# Kasli-SOC_top.net
KiCad netlist of a schematic drawn in Altium Designer
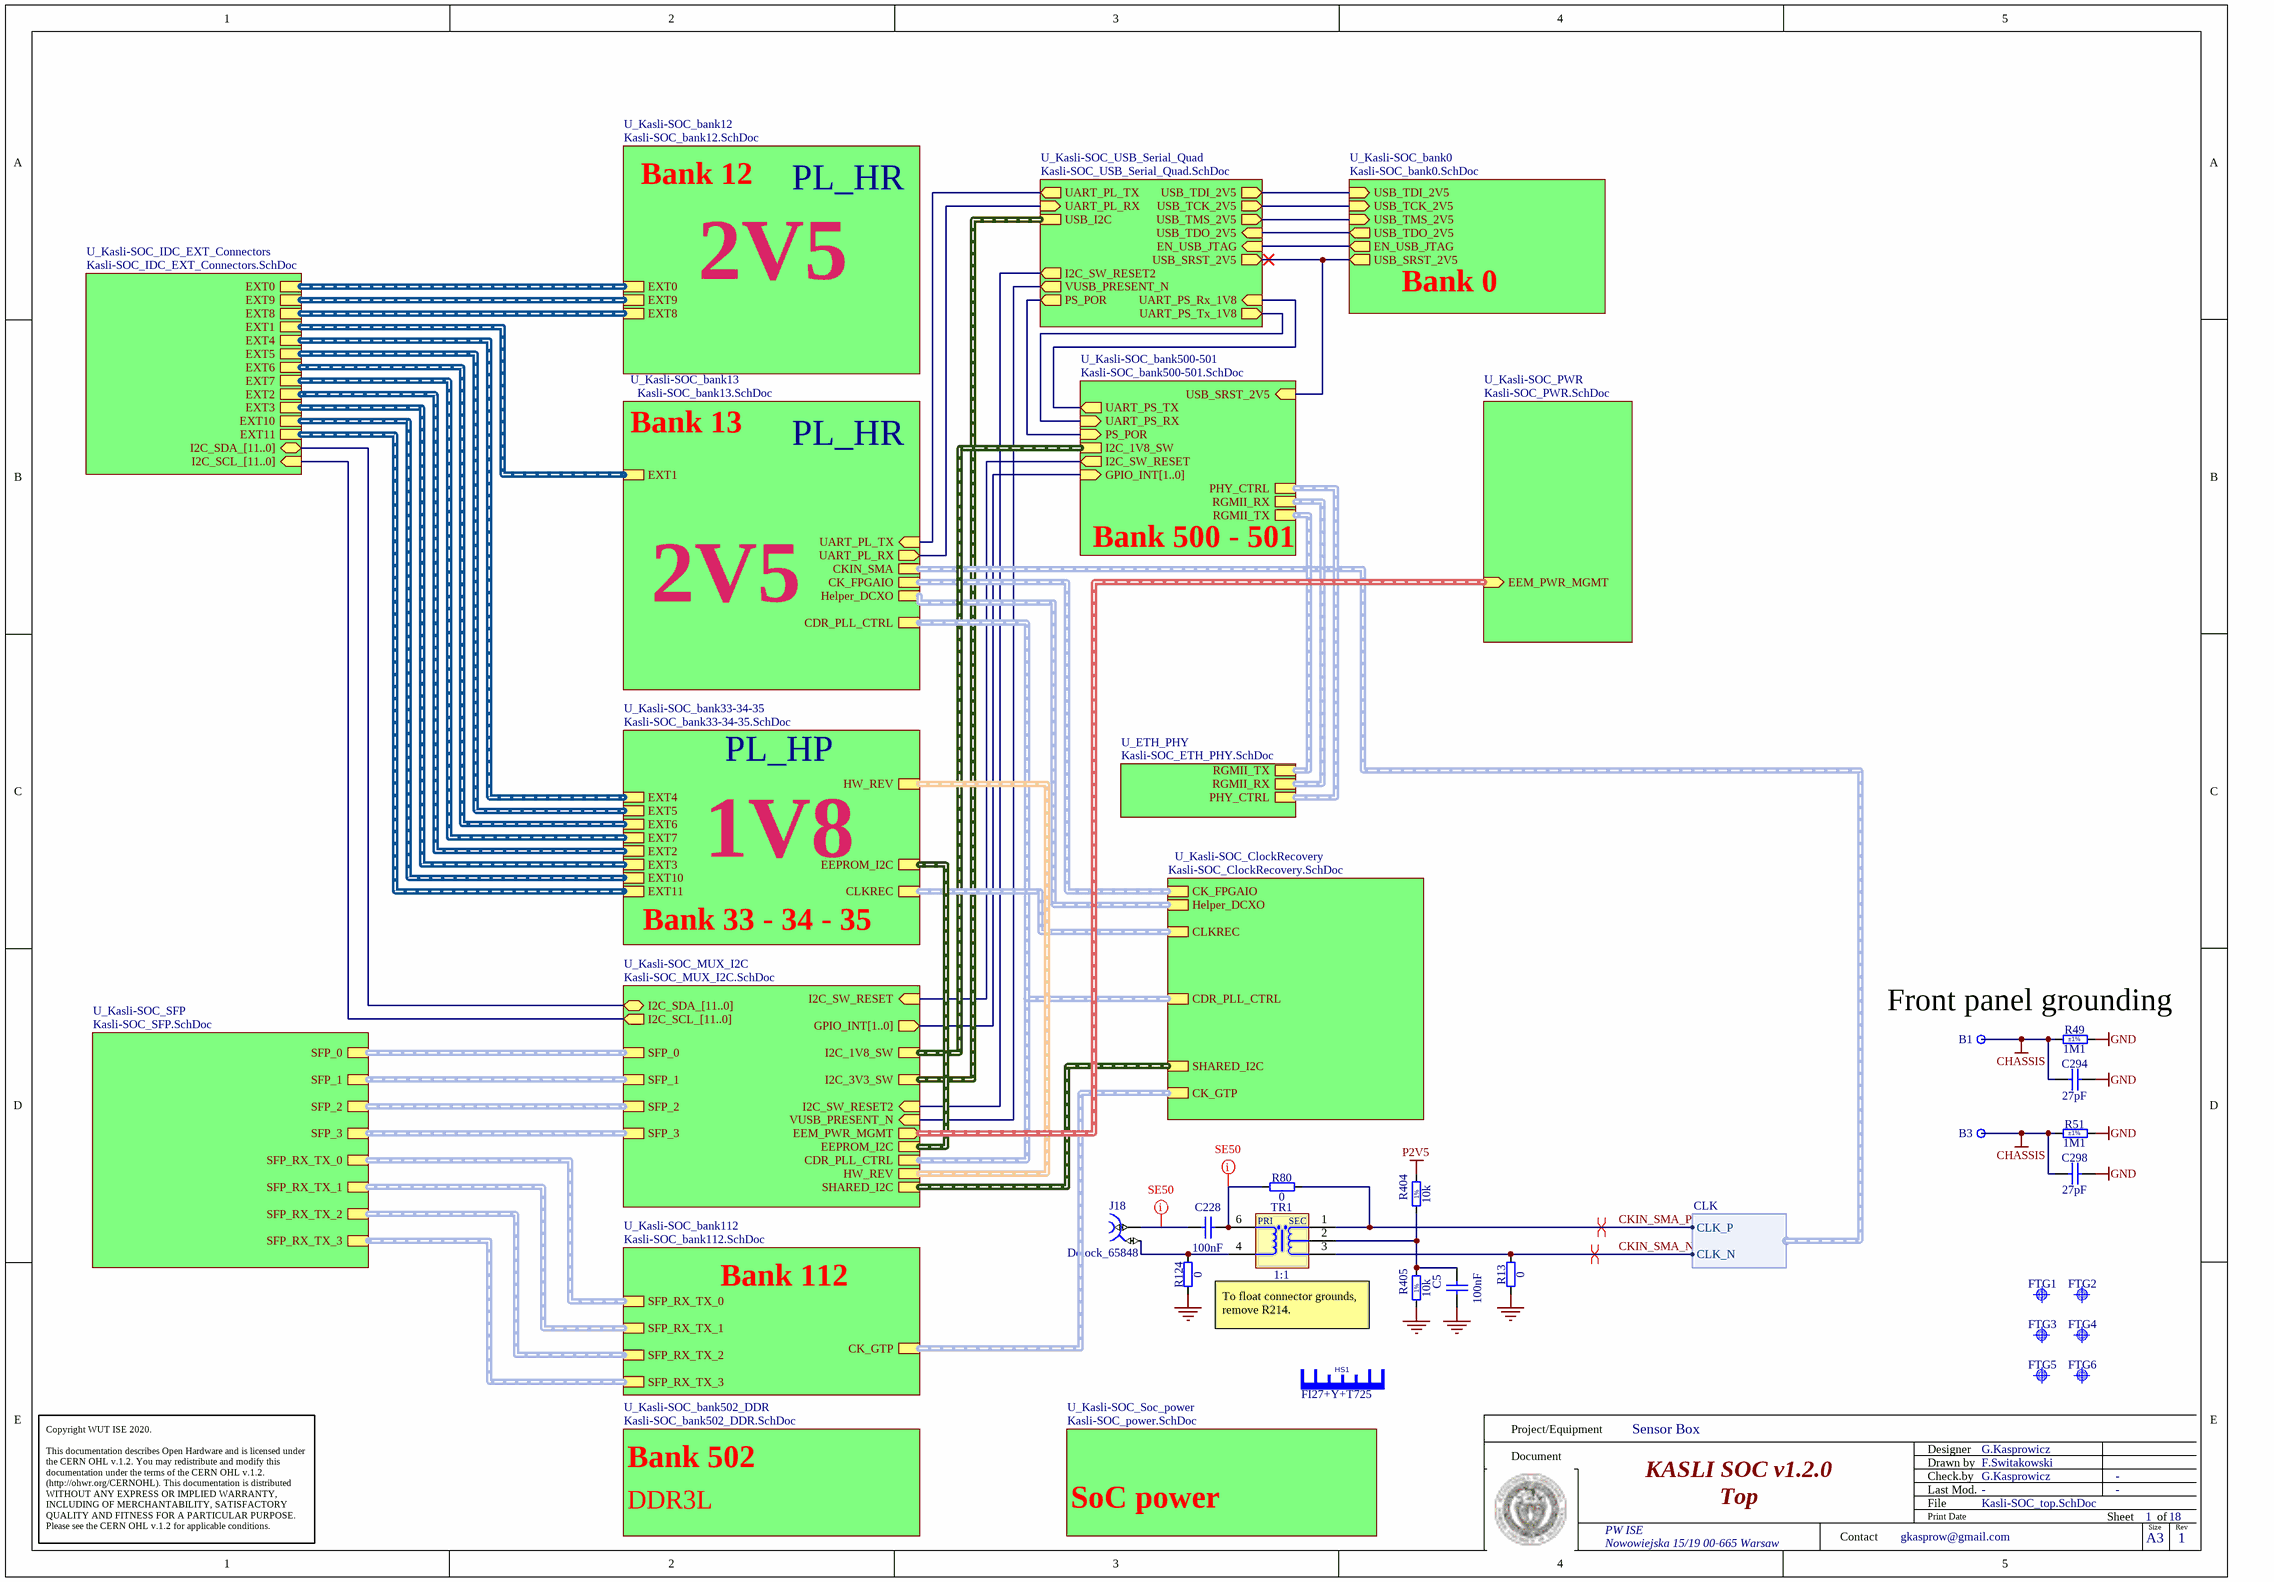
[diagram p0: Kasli-SOC_top.SchDoc]

(export (version "E")
  (design (tool "Eeschema 10.0.6"))
  (components
    (comp (ref "B1")
      (value "Plated Hole")
      (footprint "MTG270_500")
      (description "Single Terminal Socket")
      (fields (field (name "PART NUMBER") "PLATED_HOLE2.7_PAD5.0") (field (name "AUTHOR") "CERN DEM JMW"))
      (libsource (lib "Eletro-mechanical") (part "Single Terminal Socket"))
    )
    (comp (ref "B3")
      (value "Plated Hole")
      (footprint "MTG270_500")
      (description "Single Terminal Socket")
      (fields (field (name "PART NUMBER") "PLATED_HOLE2.7_PAD5.0") (field (name "AUTHOR") "CERN DEM JMW"))
      (libsource (lib "Eletro-mechanical") (part "Single Terminal Socket"))
    )
    (comp (ref "C5")
      (value "100nF")
      (footprint "CAPC0603X33N")
      (description "Non-polarised capacitor")
      (fields
        (field (name "PART NUMBER") "CC0201_100NF_6.3V_10%_X5R")
        (field (name "VOLTAGE") "6.3V")
        (field (name "AUTHOR") "CERN DEM JLC")
      )
      (libsource (lib "Capacitors") (part "Capacitor - non polarized"))
    )
    (comp (ref "C228")
      (value "100nF")
      (footprint "CAPC0603X33N")
      (description "Non-polarised capacitor")
      (fields
        (field (name "PART NUMBER") "CC0201_100NF_6.3V_10%_X5R")
        (field (name "VOLTAGE") "6.3V")
        (field (name "AUTHOR") "CERN DEM JLC")
      )
      (libsource (lib "Capacitors") (part "Capacitor - non polarized"))
    )
    (comp (ref "C294")
      (value "27pF")
      (footprint "CAPC2012X135N")
      (description "Non-polarised capacitor")
      (fields
        (field (name "PART NUMBER") "CC0805_27PF_50V_5%_NP0")
        (field (name "VOLTAGE") "50V")
        (field (name "AUTHOR") "CERN DEM JLC")
      )
      (libsource (lib "Capacitors") (part "Capacitor - non polarized"))
    )
    (comp (ref "C298")
      (value "27pF")
      (footprint "CAPC2012X135N")
      (description "Non-polarised capacitor")
      (fields
        (field (name "PART NUMBER") "CC0805_27PF_50V_5%_NP0")
        (field (name "VOLTAGE") "50V")
        (field (name "AUTHOR") "CERN DEM JLC")
      )
      (libsource (lib "Capacitors") (part "Capacitor - non polarized"))
    )
    (comp (ref "FTG1")
      (value "Use only in PCB")
      (footprint "FIDUCIAL_TOP_S100-200")
      (description "Fiducial Target")
      (fields (field (name "PART NUMBER") "FIDUCIAL_TARGET_S100-200") (field (name "AUTHOR") "CERN DEM JLC"))
      (libsource (lib "Eletro-mechanical") (part "Fiducial Target"))
    )
    (comp (ref "FTG2")
      (value "Use only in PCB")
      (footprint "FIDUCIAL_TOP_S100-200")
      (description "Fiducial Target")
      (fields (field (name "PART NUMBER") "FIDUCIAL_TARGET_S100-200") (field (name "AUTHOR") "CERN DEM JLC"))
      (libsource (lib "Eletro-mechanical") (part "Fiducial Target"))
    )
    (comp (ref "FTG3")
      (value "Use only in PCB")
      (footprint "FIDUCIAL_TOP_S100-200")
      (description "Fiducial Target")
      (fields (field (name "PART NUMBER") "FIDUCIAL_TARGET_S100-200") (field (name "AUTHOR") "CERN DEM JLC"))
      (libsource (lib "Eletro-mechanical") (part "Fiducial Target"))
    )
    (comp (ref "FTG4")
      (value "Use only in PCB")
      (footprint "FIDUCIAL_TOP_S100-200")
      (description "Fiducial Target")
      (fields (field (name "PART NUMBER") "FIDUCIAL_TARGET_S100-200") (field (name "AUTHOR") "CERN DEM JLC"))
      (libsource (lib "Eletro-mechanical") (part "Fiducial Target"))
    )
    (comp (ref "FTG5")
      (value "Use only in PCB")
      (footprint "FIDUCIAL_TOP_S100-200")
      (description "Fiducial Target")
      (fields (field (name "PART NUMBER") "FIDUCIAL_TARGET_S100-200") (field (name "AUTHOR") "CERN DEM JLC"))
      (libsource (lib "Eletro-mechanical") (part "Fiducial Target"))
    )
    (comp (ref "FTG6")
      (value "Use only in PCB")
      (footprint "FIDUCIAL_TOP_S100-200")
      (description "Fiducial Target")
      (fields (field (name "PART NUMBER") "FIDUCIAL_TARGET_S100-200") (field (name "AUTHOR") "CERN DEM JLC"))
      (libsource (lib "Eletro-mechanical") (part "Fiducial Target"))
    )
    (comp (ref "HS1")
      (value "RADIAN_FI27+Y+T725")
      (description "Heat Sink Without Pad")
      (fields
        (field (name "MANUFACTURER") "Radian Thermal Products, Inc.")
        (field (name "MANUFACTURER PART NUMBER") "FI27+Y+T725")
      )
      (libsource (lib "Schlib1") (part "RADIAN_FI23"))
    )
    (comp (ref "J18")
      (value "Delock_65848")
      (footprint "Delock_65848")
      (description "SMA connector Delock 65848")
      (libsource (lib "TechnoSystem Workspace") (part "Coax_1Female_1Shield"))
    )
    (comp (ref "R13")
      (value "0")
      (footprint "RESC1005X40N")
      (description "Resistor")
      (fields
        (field (name "PART NUMBER") "R0402_0R_JUMPER")
        (field (name "MANUFACTURER") "GENERIC")
        (field (name "AUTHOR") "CERN DEM JLC")
      )
      (libsource (lib "Resistors") (part "Resistor"))
    )
    (comp (ref "R49")
      (value "1M1")
      (footprint "RESC1608X55N")
      (description "Resistor - 1%")
      (fields
        (field (name "TOLERANCE") "±1%")
        (field (name "PART NUMBER") "R0603_1M1_1%_0.1W_100PPM")
        (field (name "POWER") "0.1W")
        (field (name "AUTHOR") "CERN DEM JLC")
      )
      (libsource (lib "Resistors") (part "Resistor - 1%"))
    )
    (comp (ref "R51")
      (value "1M1")
      (footprint "RESC1608X55N")
      (description "Resistor - 1%")
      (fields
        (field (name "TOLERANCE") "±1%")
        (field (name "PART NUMBER") "R0603_1M1_1%_0.1W_100PPM")
        (field (name "POWER") "0.1W")
        (field (name "AUTHOR") "CERN DEM JLC")
      )
      (libsource (lib "Resistors") (part "Resistor - 1%"))
    )
    (comp (ref "R80")
      (value "0")
      (footprint "RESC1005X40N")
      (description "Resistor")
      (fields
        (field (name "PART NUMBER") "R0402_0R_JUMPER")
        (field (name "MANUFACTURER") "GENERIC")
        (field (name "AUTHOR") "CERN DEM JLC")
      )
      (libsource (lib "Resistors") (part "Resistor"))
    )
    (comp (ref "R124")
      (value "0")
      (footprint "RESC1005X40N")
      (description "Resistor")
      (fields
        (field (name "PART NUMBER") "R0402_0R_JUMPER")
        (field (name "MANUFACTURER") "GENERIC")
        (field (name "AUTHOR") "CERN DEM JLC")
      )
      (libsource (lib "Resistors") (part "Resistor"))
    )
    (comp (ref "R404")
      (value "10k")
      (footprint "RESC1005X40N")
      (description "Resistor - 1%")
      (fields
        (field (name "PART NUMBER") "R0402_10K_1%_0.0625W_100PPM")
        (field (name "POWER") "0.0625W")
        (field (name "AUTHOR") "CERN DEM JLC")
      )
      (libsource (lib "") (part "Resistor - 1%_1"))
    )
    (comp (ref "R405")
      (value "10k")
      (footprint "RESC1005X40N")
      (description "Resistor - 1%")
      (fields
        (field (name "PART NUMBER") "R0402_10K_1%_0.0625W_100PPM")
        (field (name "POWER") "0.0625W")
        (field (name "AUTHOR") "CERN DEM JLC")
      )
      (libsource (lib "") (part "Resistor - 1%_1"))
    )
    (comp (ref "TR1")
      (value "1:1")
      (footprint "XFMR_MINI-CIRCUITS_AT1521")
      (description "50 Ohms 3 to 300MHz RF Transformer")
      (fields
        (field (name "PART NUMBER") "XFMR_MINI-CIRCUITS_TC2-1TX+")
        (field (name "MANUFACTURER") "MINI-CIRCUITS")
        (field (name "AUTHOR") "CERN DEM MR")
      )
      (libsource (lib "Inductors & Transformers") (part "XFMR_MINI-CIRCUITS_TC2-1TX+"))
    )
  )
  (nets
    (net (code "3") (name "/CKIN_SMA_N") (class "Default")
      (node (ref "R13") (pin "2") (pinfunction "2_2") (pintype "passive"))
      (node (ref "TR1") (pin "3") (pinfunction "S_3") (pintype "passive"))
    )
    (net (code "4") (name "/CKIN_SMA_P") (class "Default")
      (node (ref "R80") (pin "2") (pinfunction "2_2") (pintype "passive"))
      (node (ref "TR1") (pin "1") (pinfunction "SDOT_1") (pintype "passive"))
    )
    (net (code "56") (name "CHASSIS") (class "Default")
      (node (ref "B1") (pin "1") (pinfunction "1_1") (pintype "bidirectional"))
      (node (ref "B3") (pin "1") (pinfunction "1_1") (pintype "bidirectional"))
      (node (ref "C294") (pin "1") (pinfunction "1_1") (pintype "passive"))
      (node (ref "C298") (pin "1") (pinfunction "1_1") (pintype "passive"))
      (node (ref "R49") (pin "1") (pinfunction "1_1") (pintype "passive"))
      (node (ref "R51") (pin "1") (pinfunction "1_1") (pintype "passive"))
    )
    (net (code "57") (name "GND") (class "Default")
      (node (ref "C294") (pin "2") (pinfunction "2_2") (pintype "passive"))
      (node (ref "C298") (pin "2") (pinfunction "2_2") (pintype "passive"))
      (node (ref "C5") (pin "1") (pinfunction "1_1") (pintype "passive"))
      (node (ref "R124") (pin "1") (pinfunction "1_1") (pintype "passive"))
      (node (ref "R13") (pin "1") (pinfunction "1_1") (pintype "passive"))
      (node (ref "R405") (pin "1") (pinfunction "1_1") (pintype "passive"))
      (node (ref "R49") (pin "2") (pinfunction "2_2") (pintype "passive"))
      (node (ref "R51") (pin "2") (pinfunction "2_2") (pintype "passive"))
    )
    (net (code "58") (name "Net-(C228-Pad1)") (class "Default")
      (node (ref "C228") (pin "1") (pinfunction "1_1") (pintype "passive"))
      (node (ref "J18") (pin "1") (pinfunction "1_1") (pintype "bidirectional"))
    )
    (net (code "59") (name "Net-(TR1-NC)") (class "Default")
      (node (ref "C5") (pin "2") (pinfunction "2_2") (pintype "passive"))
      (node (ref "R404") (pin "1") (pinfunction "1_1") (pintype "passive"))
      (node (ref "R405") (pin "2") (pinfunction "2_2") (pintype "passive"))
      (node (ref "TR1") (pin "2") (pinfunction "NC_2") (pintype "passive"))
    )
    (net (code "60") (name "Net-(TR1-P)") (class "Default")
      (node (ref "J18") (pin "2") (pinfunction "2_2") (pintype "bidirectional"))
      (node (ref "R124") (pin "2") (pinfunction "2_2") (pintype "passive"))
      (node (ref "TR1") (pin "4") (pinfunction "P_4") (pintype "passive"))
    )
    (net (code "61") (name "Net-(TR1-PDOT)") (class "Default")
      (node (ref "C228") (pin "2") (pinfunction "2_2") (pintype "passive"))
      (node (ref "R80") (pin "1") (pinfunction "1_1") (pintype "passive"))
      (node (ref "TR1") (pin "6") (pinfunction "PDOT_6") (pintype "passive"))
    )
    (net (code "62") (name "P2V5") (class "Default")
      (node (ref "R404") (pin "2") (pinfunction "2_2") (pintype "passive"))
    )
  )
)
